# SH2_-_RS-485.net
KiCad netlist of a schematic drawn in Altium Designer
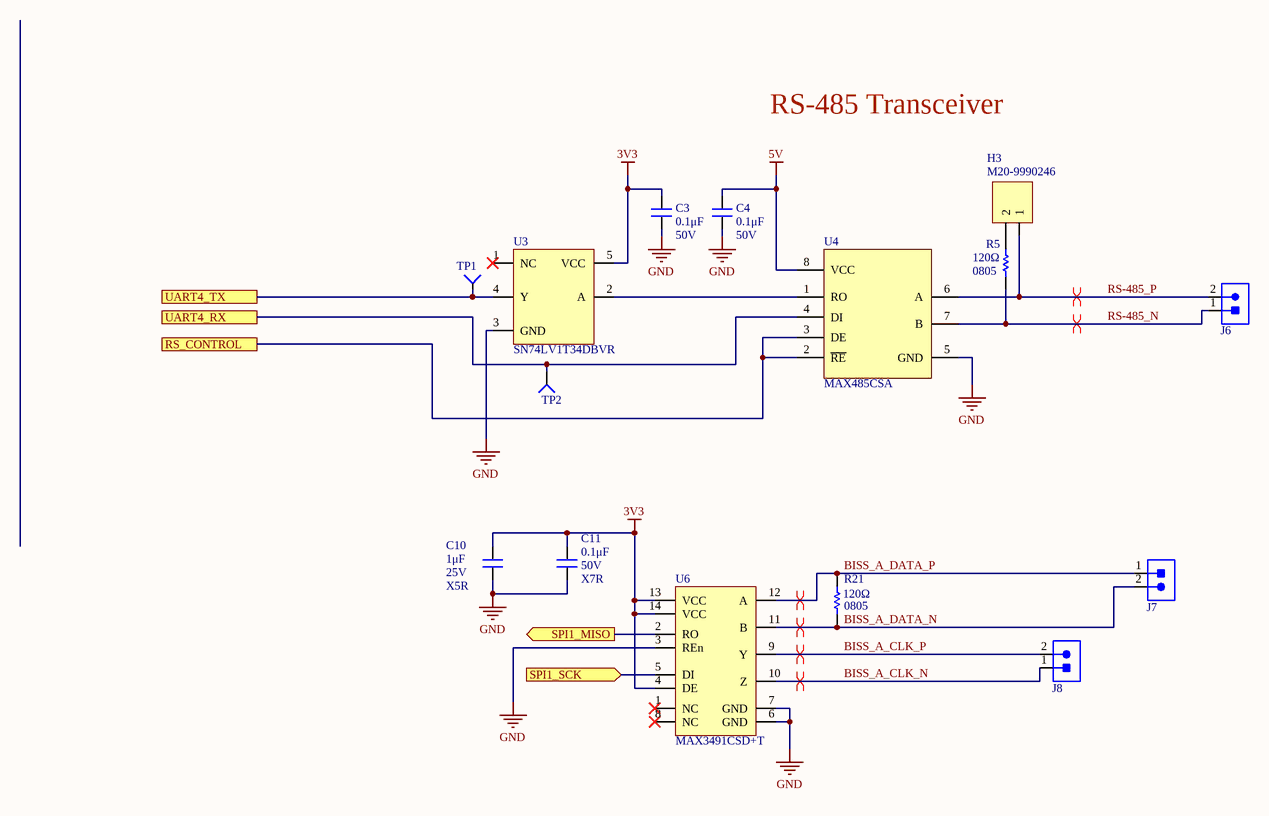
[diagram p0: SH2 - RS-485.SchDoc]

(export (version "E")
  (design (tool "Eeschema 10.0.6"))
  (components
    (comp (ref "C3")
      (value "0.1μF")
      (footprint "CAP2012")
      (description "CAP CER 0.1UF 50V X7R 0805")
      (fields
        (field (name "VOLTAGE RATING") "50V")
        (field (name "LCSC PART #") "C49678")
        (field (name "Comment") "CAP_0.1uF_50V_0805")
      )
      (libsource (lib "UWRT_Schematic_Library_2020") (part "CAP_0.1uF_50V_0805"))
    )
    (comp (ref "C4")
      (value "0.1μF")
      (footprint "CAP2012")
      (description "CAP CER 0.1UF 50V X7R 0805")
      (fields
        (field (name "VOLTAGE RATING") "50V")
        (field (name "LCSC PART #") "C49678")
        (field (name "Comment") "CAP_0.1uF_50V_0805")
      )
      (libsource (lib "UWRT_Schematic_Library_2020") (part "CAP_0.1uF_50V_0805"))
    )
    (comp (ref "C10")
      (value "1μF")
      (footprint "CAP0603")
      (description "CAP CER 1UF 25V X5R 0603")
      (fields
        (field (name "DIELECTRIC") "X5R")
        (field (name "VOLTAGE RATING") "25V")
        (field (name "Comment") "CAP_1uF_25V_0603")
      )
      (libsource (lib "UWRT_Schematic_Library_2020") (part "CAP_1uF_25V_0603"))
    )
    (comp (ref "C11")
      (value "0.1μF")
      (footprint "CAP0603")
      (description "CAP CER 0.1UF 50V X7R 0603")
      (fields
        (field (name "DIELECTRIC") "X7R")
        (field (name "VOLTAGE RATING") "50V")
        (field (name "Comment") "CAP_0.1uF_50V_0603")
      )
      (libsource (lib "UWRT_Schematic_Library_2020") (part "CAP_0.1uF_50V_0603"))
    )
    (comp (ref "H3")
      (value "JUMPER")
      (footprint "HDR1X2")
      (description "HEADER 2X1")
      (fields (field (name "MANUFACTURER PART NUMBER 1") "M20-9990246"))
      (libsource (lib "UWRT_Schematic_Library_2020") (part "JUMPER"))
    )
    (comp (ref "J6")
      (value "CON_2POS_SCREW_TERM")
      (footprint "1935161")
      (description "TERM BLK 2POS SIDE ENTRY 5MM")
      (libsource (lib "UWRT_Schematic_Library_2020") (part "CON_2POS_SCREW_TERM"))
    )
    (comp (ref "J7")
      (value "CON_2POS_SCREW_TERM")
      (footprint "1935161")
      (description "TERM BLK 2POS SIDE ENTRY 5MM")
      (libsource (lib "") (part "CON_2POS_SCREW_TERM_1"))
    )
    (comp (ref "J8")
      (value "CON_2POS_SCREW_TERM")
      (footprint "1935161")
      (description "TERM BLK 2POS SIDE ENTRY 5MM")
      (libsource (lib "UWRT_Schematic_Library_2020") (part "CON_2POS_SCREW_TERM"))
    )
    (comp (ref "R5")
      (value "120Ω")
      (footprint "RESC0805")
      (description "RES 120 OHM 1% 1/8W 0805")
      (fields
        (field (name "LCSC PART #") "C17437")
        (field (name "PACKAGE/FOOTPRINT") "0805")
        (field (name "Comment") "RES_120Ω_0805_1%")
      )
      (libsource (lib "UWRT_Schematic_Library_2020") (part "RES_120Ω_0805_1%"))
    )
    (comp (ref "R21")
      (value "120Ω")
      (footprint "RESC0805")
      (description "RES 120 OHM 1% 1/8W 0805")
      (fields
        (field (name "PACKAGE/FOOTPRINT") "0805")
        (field (name "LCSC PART #") "C17437")
        (field (name "Comment") "RES_120Ω_0805_1%")
      )
      (libsource (lib "UWRT_Schematic_Library_2020") (part "RES_120Ω_0805_1%"))
    )
    (comp (ref "TP1")
      (value "TESTPOINT_1MM_CIRCLE")
      (footprint "TESTPOINT_CIRCLE_1MM")
      (description "TESTPOINT 1MM CIRCLE")
      (libsource (lib "UWRT_Schematic_Library_2020") (part "TESTPOINT_1MM_CIRCLE"))
    )
    (comp (ref "TP2")
      (value "TESTPOINT_1MM_CIRCLE")
      (footprint "TESTPOINT_CIRCLE_1MM")
      (description "TESTPOINT 1MM CIRCLE")
      (libsource (lib "UWRT_Schematic_Library_2020") (part "TESTPOINT_1MM_CIRCLE"))
    )
    (comp (ref "U3")
      (value "IC_BUFFER")
      (footprint "SN74LV1T34DBVR")
      (description "IC BUF NON-INVERT 5.5V SOT23-5")
      (fields
        (field (name "MANUFACTURER PART NUMBER 1") "SN74LV1T34DBVR")
        (field (name "LCSC PART #") "C100024")
      )
      (libsource (lib "UWRT_Schematic_Library_2020") (part "IC_BUFFER"))
    )
    (comp (ref "U4")
      (value "MAX485CSA")
      (footprint "SOIC127P600X175-8N")
      (description "IC RS485 TRANSCEIVER HALF 1/1 8SOIC")
      (fields (field (name "LCSC PART #") "C9945"))
      (libsource (lib "UWRT_Schematic_Library_2020") (part "MAX485CSA"))
    )
    (comp (ref "U6")
      (value "MAX3491")
      (footprint "MAX3491CSD+T")
      (description "IC RS485 TRANSCEIVER FULL 1/1 14SOIC")
      (fields (field (name "MANUFACTURER PART NUMBER 1") "MAX3491CSD+T"))
      (libsource (lib "UWRT_Schematic_Library_2020") (part "MAX3491"))
    )
  )
  (nets
    (net (code "1") (name "/BISS_A_CLK_N") (class "Default")
      (node (ref "J8") (pin "1") (pinfunction "1_1") (pintype "passive"))
      (node (ref "U6") (pin "10") (pinfunction "Z_10") (pintype "passive"))
    )
    (net (code "2") (name "/BISS_A_CLK_P") (class "Default")
      (node (ref "J8") (pin "2") (pinfunction "2_2") (pintype "passive"))
      (node (ref "U6") (pin "9") (pinfunction "Y_9") (pintype "passive"))
    )
    (net (code "3") (name "/BISS_A_DATA_N") (class "Default")
      (node (ref "J7") (pin "2") (pinfunction "2_2") (pintype "passive"))
      (node (ref "R21") (pin "1") (pinfunction "1_1") (pintype "passive"))
      (node (ref "U6") (pin "11") (pinfunction "B_11") (pintype "passive"))
    )
    (net (code "4") (name "/BISS_A_DATA_P") (class "Default")
      (node (ref "J7") (pin "1") (pinfunction "1_1") (pintype "passive"))
      (node (ref "R21") (pin "2") (pinfunction "2_2") (pintype "passive"))
      (node (ref "U6") (pin "12") (pinfunction "A_12") (pintype "passive"))
    )
    (net (code "5") (name "/RS-485_N") (class "Default")
      (node (ref "J6") (pin "1") (pinfunction "1_1") (pintype "passive"))
      (node (ref "R5") (pin "1") (pinfunction "1_1") (pintype "passive"))
      (node (ref "U4") (pin "7") (pinfunction "B_7") (pintype "passive"))
    )
    (net (code "6") (name "/RS-485_P") (class "Default")
      (node (ref "H3") (pin "1") (pinfunction "1_1") (pintype "passive"))
      (node (ref "J6") (pin "2") (pinfunction "2_2") (pintype "passive"))
      (node (ref "U4") (pin "6") (pinfunction "A_6") (pintype "passive"))
    )
    (net (code "7") (name "/RS_CONTROL") (class "Default")
      (node (ref "U4") (pin "2") (pinfunction "~{RE}_2") (pintype "passive"))
      (node (ref "U4") (pin "3") (pinfunction "DE_3") (pintype "passive"))
    )
    (net (code "8") (name "/SPI1_MISO") (class "Default")
      (node (ref "U6") (pin "2") (pinfunction "RO_2") (pintype "passive"))
    )
    (net (code "9") (name "/SPI1_SCK") (class "Default")
      (node (ref "U6") (pin "5") (pinfunction "DI_5") (pintype "passive"))
    )
    (net (code "10") (name "/UART4_RX") (class "Default")
      (node (ref "TP2") (pin "1") (pinfunction "=value_1") (pintype "passive"))
      (node (ref "U4") (pin "4") (pinfunction "DI_4") (pintype "passive"))
    )
    (net (code "11") (name "/UART4_TX") (class "Default")
      (node (ref "TP1") (pin "1") (pinfunction "=value_1") (pintype "passive"))
      (node (ref "U3") (pin "4") (pinfunction "Y_4") (pintype "passive"))
    )
    (net (code "12") (name "3V3") (class "Default")
      (node (ref "C10") (pin "2") (pinfunction "2_2") (pintype "passive"))
      (node (ref "C11") (pin "2") (pinfunction "2_2") (pintype "passive"))
      (node (ref "C3") (pin "1") (pinfunction "1_1") (pintype "passive"))
      (node (ref "U3") (pin "5") (pinfunction "VCC_5") (pintype "passive"))
      (node (ref "U6") (pin "13") (pinfunction "VCC_13") (pintype "passive"))
      (node (ref "U6") (pin "14") (pinfunction "VCC_14") (pintype "passive"))
      (node (ref "U6") (pin "4") (pinfunction "DE_4") (pintype "passive"))
    )
    (net (code "13") (name "5V") (class "Default")
      (node (ref "C4") (pin "1") (pinfunction "1_1") (pintype "passive"))
      (node (ref "U4") (pin "8") (pinfunction "VCC_8") (pintype "power_in"))
    )
    (net (code "14") (name "GND") (class "Default")
      (node (ref "C10") (pin "1") (pinfunction "1_1") (pintype "passive"))
      (node (ref "C11") (pin "1") (pinfunction "1_1") (pintype "passive"))
      (node (ref "C3") (pin "2") (pinfunction "2_2") (pintype "passive"))
      (node (ref "C4") (pin "2") (pinfunction "2_2") (pintype "passive"))
      (node (ref "U3") (pin "3") (pinfunction "GND_3") (pintype "passive"))
      (node (ref "U4") (pin "5") (pinfunction "GND_5") (pintype "power_in"))
      (node (ref "U6") (pin "3") (pinfunction "REn_3") (pintype "passive"))
      (node (ref "U6") (pin "6") (pinfunction "GND_6") (pintype "passive"))
      (node (ref "U6") (pin "7") (pinfunction "GND_7") (pintype "passive"))
    )
    (net (code "15") (name "Net-(H3-Pad2)") (class "Default")
      (node (ref "H3") (pin "2") (pinfunction "2_2") (pintype "passive"))
      (node (ref "R5") (pin "2") (pinfunction "2_2") (pintype "passive"))
    )
    (net (code "16") (name "Net-(U3-A)") (class "Default")
      (node (ref "U3") (pin "2") (pinfunction "A_2") (pintype "passive"))
      (node (ref "U4") (pin "1") (pinfunction "RO_1") (pintype "passive"))
    )
    (net (code "17") (name "unconnected-(U3-NC-Pad1)") (class "Default")
      (node (ref "U3") (pin "1") (pinfunction "NC_1") (pintype "passive+no_connect"))
    )
    (net (code "18") (name "unconnected-(U6-NC-Pad1)") (class "Default")
      (node (ref "U6") (pin "1") (pinfunction "NC_1") (pintype "passive+no_connect"))
    )
    (net (code "19") (name "unconnected-(U6-NC-Pad8)") (class "Default")
      (node (ref "U6") (pin "8") (pinfunction "NC_8") (pintype "passive+no_connect"))
    )
  )
)
